# IMU.net
KiCad netlist of a schematic drawn in Altium Designer
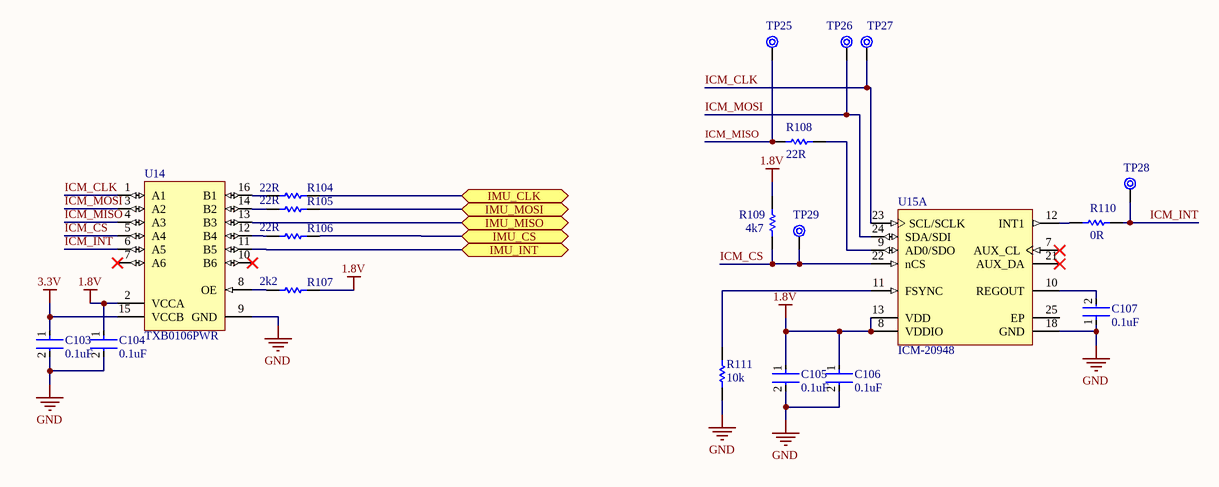
[diagram p0: IMU.SchDoc]

(export (version "E")
  (design (tool "Eeschema 10.0.6"))
  (components
    (comp (ref "C103")
      (value "0.1uF")
      (footprint "FP-C0805C-DN-MFG")
      (description "CAP CER 0.1UF 50V X7R 0805")
      (fields
        (field (name "MANUFACTURER PART NUMBER") "C0805C104K5RACTU")
        (field (name "MANUFACTURER") "KEMET")
      )
      (libsource (lib "Altium Content Vault") (part "b4654b650e69147ec39a6b967a45e02"))
    )
    (comp (ref "C104")
      (value "0.1uF")
      (footprint "FP-C0805C-DN-MFG")
      (description "CAP CER 0.1UF 50V X7R 0805")
      (fields
        (field (name "MANUFACTURER PART NUMBER") "C0805C104K5RACTU")
        (field (name "MANUFACTURER") "KEMET")
      )
      (libsource (lib "Altium Content Vault") (part "b4654b650e69147ec39a6b967a45e02"))
    )
    (comp (ref "C105")
      (value "0.1uF")
      (footprint "FP-C0805C-DN-MFG")
      (description "CAP CER 0.1UF 50V X7R 0805")
      (fields
        (field (name "MANUFACTURER PART NUMBER") "C0805C104K5RACTU")
        (field (name "MANUFACTURER") "KEMET")
      )
      (libsource (lib "Altium Content Vault") (part "b4654b650e69147ec39a6b967a45e02"))
    )
    (comp (ref "C106")
      (value "0.1uF")
      (footprint "FP-C0805C-DN-MFG")
      (description "CAP CER 0.1UF 50V X7R 0805")
      (fields
        (field (name "MANUFACTURER PART NUMBER") "C0805C104K5RACTU")
        (field (name "MANUFACTURER") "KEMET")
      )
      (libsource (lib "Altium Content Vault") (part "b4654b650e69147ec39a6b967a45e02"))
    )
    (comp (ref "C107")
      (value "0.1uF")
      (footprint "FP-C0805C-DN-MFG")
      (description "CAP CER 0.1UF 50V X7R 0805")
      (fields
        (field (name "MANUFACTURER PART NUMBER") "C0805C104K5RACTU")
        (field (name "MANUFACTURER") "KEMET")
      )
      (libsource (lib "Altium Content Vault") (part "b4654b650e69147ec39a6b967a45e02"))
    )
    (comp (ref "R104")
      (value "22R")
      (footprint "RESC2013X50X30LL20T20")
      (description "0805")
      (fields (field (name "MANUFACTURER") "Vishay Dale") (field (name "PART NUMBER") "CRCW08050000Z0EA"))
      (libsource (lib "Altium Content Vault") (part "RES"))
    )
    (comp (ref "R105")
      (value "22R")
      (footprint "RESC2013X50X30LL20T20")
      (description "0805")
      (fields (field (name "MANUFACTURER") "Vishay Dale") (field (name "PART NUMBER") "CRCW08050000Z0EA"))
      (libsource (lib "Altium Content Vault") (part "RES"))
    )
    (comp (ref "R106")
      (value "22R")
      (footprint "RESC2013X50X30LL20T20")
      (description "0805")
      (fields (field (name "MANUFACTURER") "Vishay Dale") (field (name "PART NUMBER") "CRCW08050000Z0EA"))
      (libsource (lib "Altium Content Vault") (part "RES"))
    )
    (comp (ref "R107")
      (value "2k2")
      (footprint "RESC2013X50X30LL20T20")
      (description "0805")
      (fields (field (name "MANUFACTURER") "Vishay Dale") (field (name "PART NUMBER") "CRCW08050000Z0EA"))
      (libsource (lib "Altium Content Vault") (part "RES"))
    )
    (comp (ref "R108")
      (value "22R")
      (footprint "RESC2013X50X30LL20T20")
      (description "0805")
      (fields (field (name "MANUFACTURER") "Vishay Dale") (field (name "PART NUMBER") "CRCW08050000Z0EA"))
      (libsource (lib "Altium Content Vault") (part "RES"))
    )
    (comp (ref "R109")
      (value "4k7")
      (footprint "RESC2013X50X30LL20T20")
      (description "0805")
      (fields (field (name "MANUFACTURER") "Vishay Dale") (field (name "PART NUMBER") "CRCW08050000Z0EA"))
      (libsource (lib "Altium Content Vault") (part "RES"))
    )
    (comp (ref "R110")
      (value "0R")
      (footprint "RESC1609X50X30NL8T20")
      (description "Chip Resistor, 0 Ohm, Jumper, 100 mW, -55 to 155 degC, 0603 (1608 Metric), RoHS, Tape and Reel")
      (fields (field (name "MANUFACTURER") "Vishay Semiconductor"))
      (libsource (lib "Altium Content Vault") (part "RES-2"))
    )
    (comp (ref "R111")
      (value "10k")
      (footprint "RESC2013X50X30LL20T20")
      (description "0805")
      (fields (field (name "MANUFACTURER") "Vishay Dale") (field (name "PART NUMBER") "CRCW08050000Z0EA"))
      (libsource (lib "Altium Content Vault") (part "RES"))
    )
    (comp (ref "TP25")
      (value "Test Point 1mm")
      (footprint "Pad 1mm")
      (libsource (lib "OTHER") (part "Test Point 1mm"))
    )
    (comp (ref "TP26")
      (value "Test Point 1mm")
      (footprint "Pad 1mm")
      (libsource (lib "OTHER") (part "Test Point 1mm"))
    )
    (comp (ref "TP27")
      (value "Test Point 1mm")
      (footprint "Pad 1mm")
      (libsource (lib "OTHER") (part "Test Point 1mm"))
    )
    (comp (ref "TP28")
      (value "Test Point 1mm")
      (footprint "Pad 1mm")
      (libsource (lib "OTHER") (part "Test Point 1mm"))
    )
    (comp (ref "TP29")
      (value "Test Point 1mm")
      (footprint "Pad 1mm")
      (libsource (lib "OTHER") (part "Test Point 1mm"))
    )
    (comp (ref "U14")
      (value "TXB0106PWR")
      (footprint "PW0016A_L")
      (fields (field (name "MANUFACTURER") "Texas Instruments"))
      (libsource (lib "Altium Content Vault") (part "TI-TXB0106-TSSOP_PW-16"))
    )
    (comp (ref "U15")
      (value "ICM-20948")
      (footprint "TDK-QFN-24_L")
      (fields (field (name "MANUFACTURER") "TDK"))
      (libsource (lib "Altium Content Vault") (part "TDK-ICM-20948-QFN-24"))
    )
  )
  (nets
    (net (code "1") (name "/ICM_CLK") (class "Default")
      (node (ref "TP27") (pin "1") (pinfunction "1_1") (pintype "passive"))
      (node (ref "U14") (pin "1") (pinfunction "A1_1") (pintype "bidirectional"))
      (node (ref "U15") (pin "23") (pinfunction "SCL/SCLK_23") (pintype "input"))
    )
    (net (code "2") (name "/ICM_CS") (class "Default")
      (node (ref "R109") (pin "1") (pinfunction "1_1") (pintype "passive"))
      (node (ref "TP29") (pin "1") (pinfunction "1_1") (pintype "passive"))
      (node (ref "U14") (pin "5") (pinfunction "A4_5") (pintype "bidirectional"))
      (node (ref "U15") (pin "22") (pinfunction "nCS_22") (pintype "input"))
    )
    (net (code "3") (name "/ICM_INT") (class "Default")
      (node (ref "R110") (pin "2") (pinfunction "2_2") (pintype "passive"))
      (node (ref "TP28") (pin "1") (pinfunction "1_1") (pintype "passive"))
      (node (ref "U14") (pin "6") (pinfunction "A5_6") (pintype "bidirectional"))
    )
    (net (code "4") (name "/ICM_MISO") (class "Default")
      (node (ref "R108") (pin "1") (pinfunction "1_1") (pintype "passive"))
      (node (ref "TP25") (pin "1") (pinfunction "1_1") (pintype "passive"))
      (node (ref "U14") (pin "4") (pinfunction "A3_4") (pintype "bidirectional"))
    )
    (net (code "5") (name "/ICM_MOSI") (class "Default")
      (node (ref "TP26") (pin "1") (pinfunction "1_1") (pintype "passive"))
      (node (ref "U14") (pin "3") (pinfunction "A2_3") (pintype "bidirectional"))
      (node (ref "U15") (pin "24") (pinfunction "SDA/SDI_24") (pintype "bidirectional"))
    )
    (net (code "6") (name "/IMU_CLK") (class "Default")
      (node (ref "R104") (pin "2") (pinfunction "2_2") (pintype "passive"))
    )
    (net (code "7") (name "/IMU_CS") (class "Default")
      (node (ref "R106") (pin "2") (pinfunction "2_2") (pintype "passive"))
    )
    (net (code "8") (name "/IMU_INT") (class "Default")
      (node (ref "U14") (pin "11") (pinfunction "B5_11") (pintype "bidirectional"))
    )
    (net (code "9") (name "/IMU_MISO") (class "Default")
      (node (ref "U14") (pin "13") (pinfunction "B3_13") (pintype "bidirectional"))
    )
    (net (code "10") (name "/IMU_MOSI") (class "Default")
      (node (ref "R105") (pin "2") (pinfunction "2_2") (pintype "passive"))
    )
    (net (code "11") (name "1.8V") (class "Default")
      (node (ref "C104") (pin "1") (pinfunction "1_1") (pintype "passive"))
      (node (ref "C105") (pin "1") (pinfunction "1_1") (pintype "passive"))
      (node (ref "C106") (pin "1") (pinfunction "1_1") (pintype "passive"))
      (node (ref "R107") (pin "2") (pinfunction "2_2") (pintype "passive"))
      (node (ref "R109") (pin "2") (pinfunction "2_2") (pintype "passive"))
      (node (ref "U14") (pin "2") (pinfunction "VCCA_2") (pintype "power_in"))
      (node (ref "U15") (pin "13") (pinfunction "VDD_13") (pintype "power_in"))
      (node (ref "U15") (pin "8") (pinfunction "VDDIO_8") (pintype "power_in"))
    )
    (net (code "12") (name "3.3V") (class "Default")
      (node (ref "C103") (pin "1") (pinfunction "1_1") (pintype "passive"))
      (node (ref "U14") (pin "15") (pinfunction "VCCB_15") (pintype "power_in"))
    )
    (net (code "13") (name "GND") (class "Default")
      (node (ref "C103") (pin "2") (pinfunction "2_2") (pintype "passive"))
      (node (ref "C104") (pin "2") (pinfunction "2_2") (pintype "passive"))
      (node (ref "C105") (pin "2") (pinfunction "2_2") (pintype "passive"))
      (node (ref "C106") (pin "2") (pinfunction "2_2") (pintype "passive"))
      (node (ref "C107") (pin "1") (pinfunction "1_1") (pintype "passive"))
      (node (ref "R111") (pin "1") (pinfunction "1_1") (pintype "passive"))
      (node (ref "U14") (pin "9") (pinfunction "GND_9") (pintype "power_in"))
      (node (ref "U15") (pin "18") (pinfunction "GND_18") (pintype "power_in"))
    )
    (net (code "14") (name "Net-(U14-B1)") (class "Default")
      (node (ref "R104") (pin "1") (pinfunction "1_1") (pintype "passive"))
      (node (ref "U14") (pin "16") (pinfunction "B1_16") (pintype "bidirectional"))
    )
    (net (code "15") (name "Net-(U14-B2)") (class "Default")
      (node (ref "R105") (pin "1") (pinfunction "1_1") (pintype "passive"))
      (node (ref "U14") (pin "14") (pinfunction "B2_14") (pintype "bidirectional"))
    )
    (net (code "16") (name "Net-(U14-B4)") (class "Default")
      (node (ref "R106") (pin "1") (pinfunction "1_1") (pintype "passive"))
      (node (ref "U14") (pin "12") (pinfunction "B4_12") (pintype "bidirectional"))
    )
    (net (code "17") (name "Net-(U14-OE)") (class "Default")
      (node (ref "R107") (pin "1") (pinfunction "1_1") (pintype "passive"))
      (node (ref "U14") (pin "8") (pinfunction "OE_8") (pintype "input"))
    )
    (net (code "18") (name "Net-(U15A-AD0{slash}SDO)") (class "Default")
      (node (ref "R108") (pin "2") (pinfunction "2_2") (pintype "passive"))
      (node (ref "U15") (pin "9") (pinfunction "AD0/SDO_9") (pintype "bidirectional"))
    )
    (net (code "19") (name "Net-(U15A-FSYNC)") (class "Default")
      (node (ref "R111") (pin "2") (pinfunction "2_2") (pintype "passive"))
      (node (ref "U15") (pin "11") (pinfunction "FSYNC_11") (pintype "input"))
    )
    (net (code "20") (name "Net-(U15A-INT1)") (class "Default")
      (node (ref "R110") (pin "1") (pinfunction "1_1") (pintype "passive"))
      (node (ref "U15") (pin "12") (pinfunction "INT1_12") (pintype "output"))
    )
    (net (code "21") (name "Net-(U15A-REGOUT)") (class "Default")
      (node (ref "C107") (pin "2") (pinfunction "2_2") (pintype "passive"))
      (node (ref "U15") (pin "10") (pinfunction "REGOUT_10") (pintype "passive"))
    )
    (net (code "22") (name "unconnected-(U14-A6-Pad7)") (class "Default")
      (node (ref "U14") (pin "7") (pinfunction "A6_7") (pintype "bidirectional+no_connect"))
    )
    (net (code "23") (name "unconnected-(U14-B6-Pad10)") (class "Default")
      (node (ref "U14") (pin "10") (pinfunction "B6_10") (pintype "bidirectional+no_connect"))
    )
    (net (code "24") (name "unconnected-(U15A-AUX_CL-Pad7)") (class "Default")
      (node (ref "U15") (pin "7") (pinfunction "AUX_CL_7") (pintype "input+no_connect"))
    )
    (net (code "25") (name "unconnected-(U15A-AUX_DA-Pad21)") (class "Default")
      (node (ref "U15") (pin "21") (pinfunction "AUX_DA_21") (pintype "passive+no_connect"))
    )
    (net (code "26") (name "unconnected-(U15A-EP-Pad25)") (class "Default")
      (node (ref "U15") (pin "25") (pinfunction "EP_25") (pintype "passive"))
    )
  )
)
